# Bats-n-Gons2.net
KiCad netlist of a schematic drawn in EAGLE
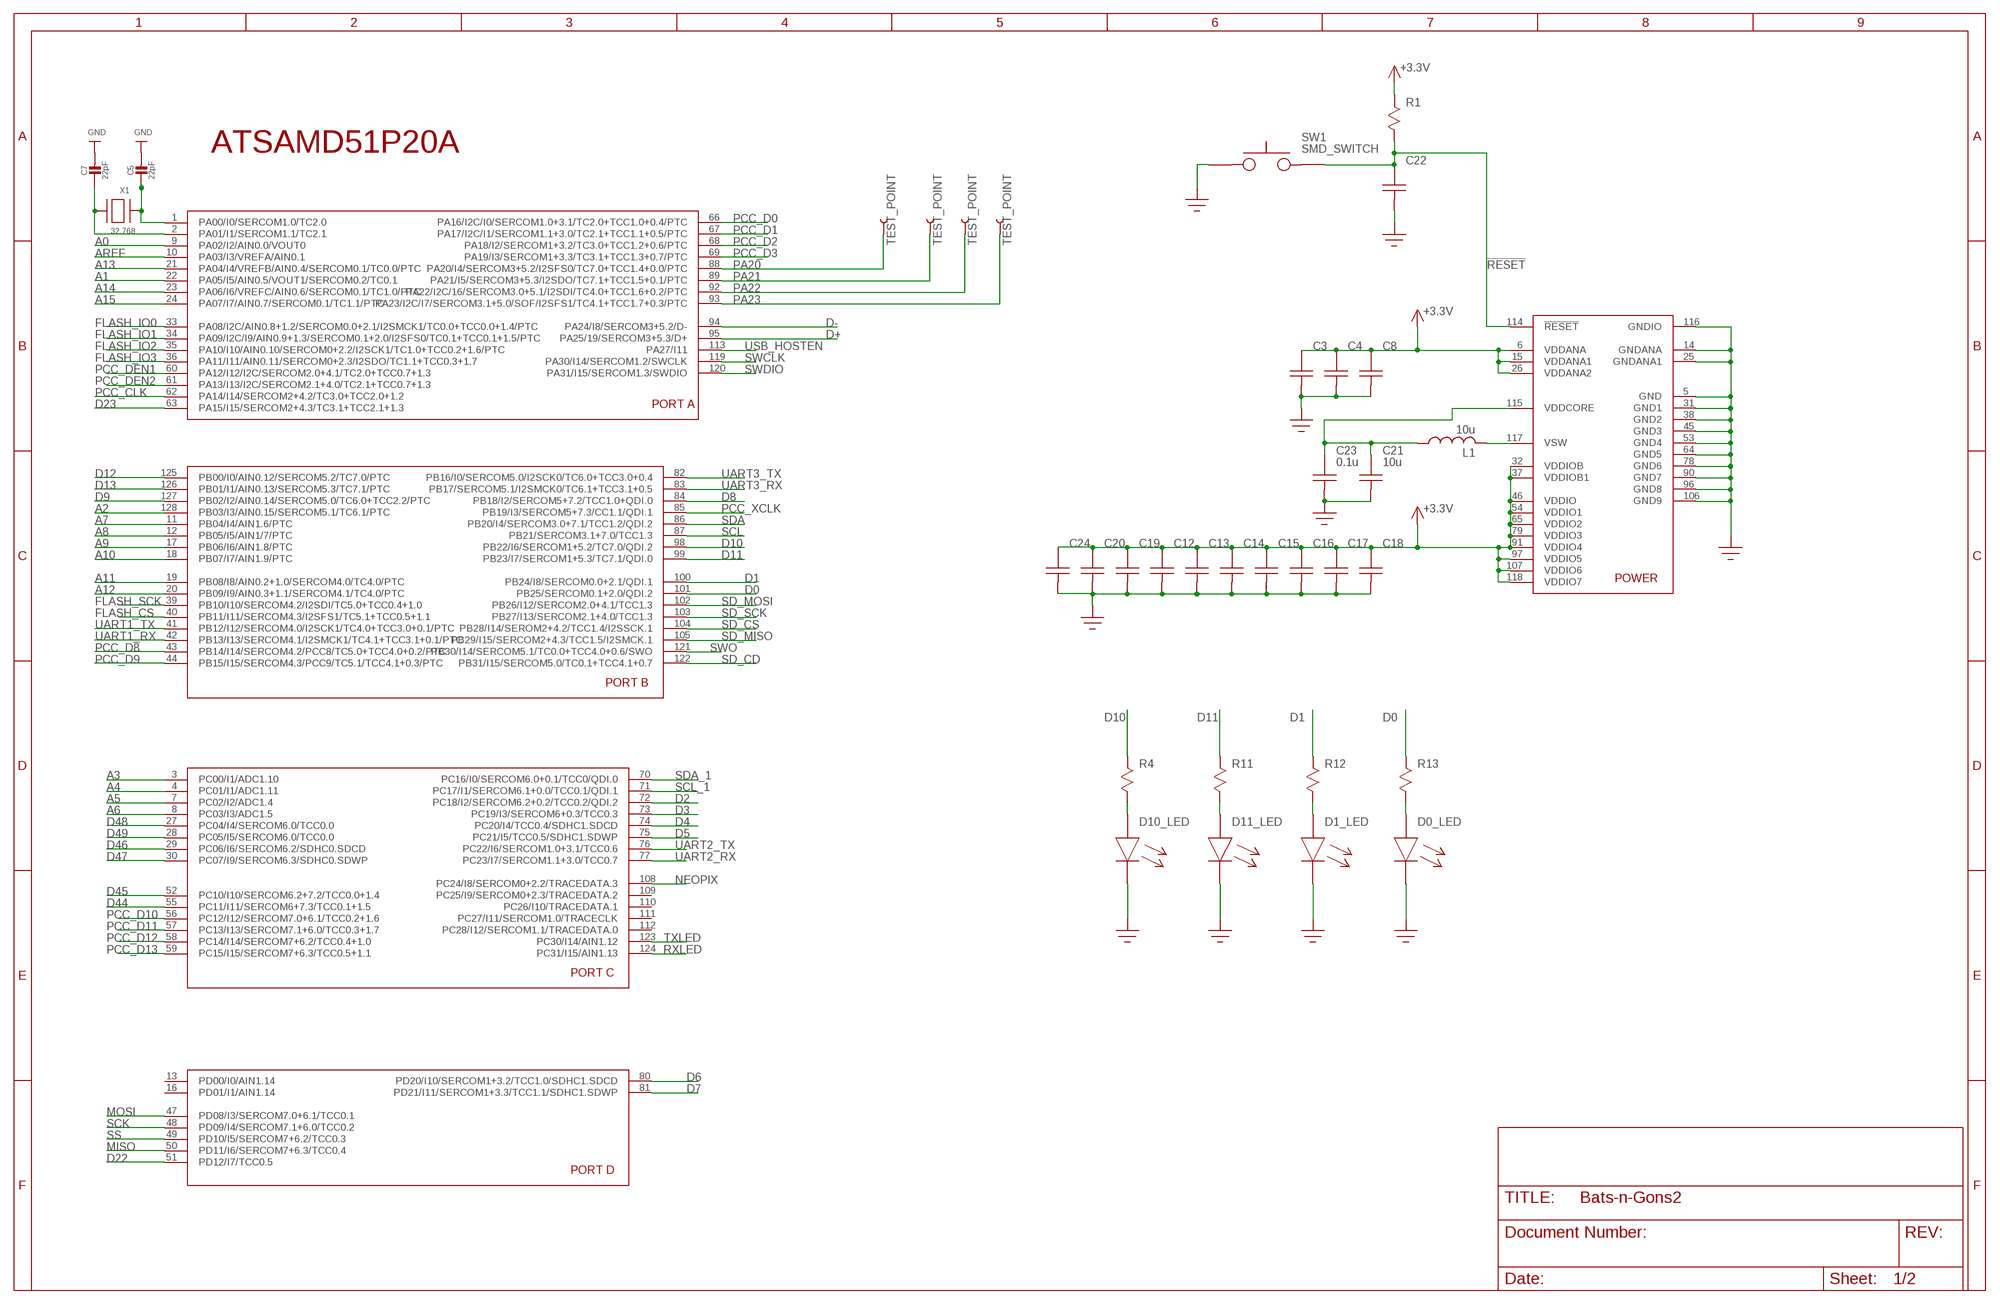
[diagram p0: schematic, sheet 1]
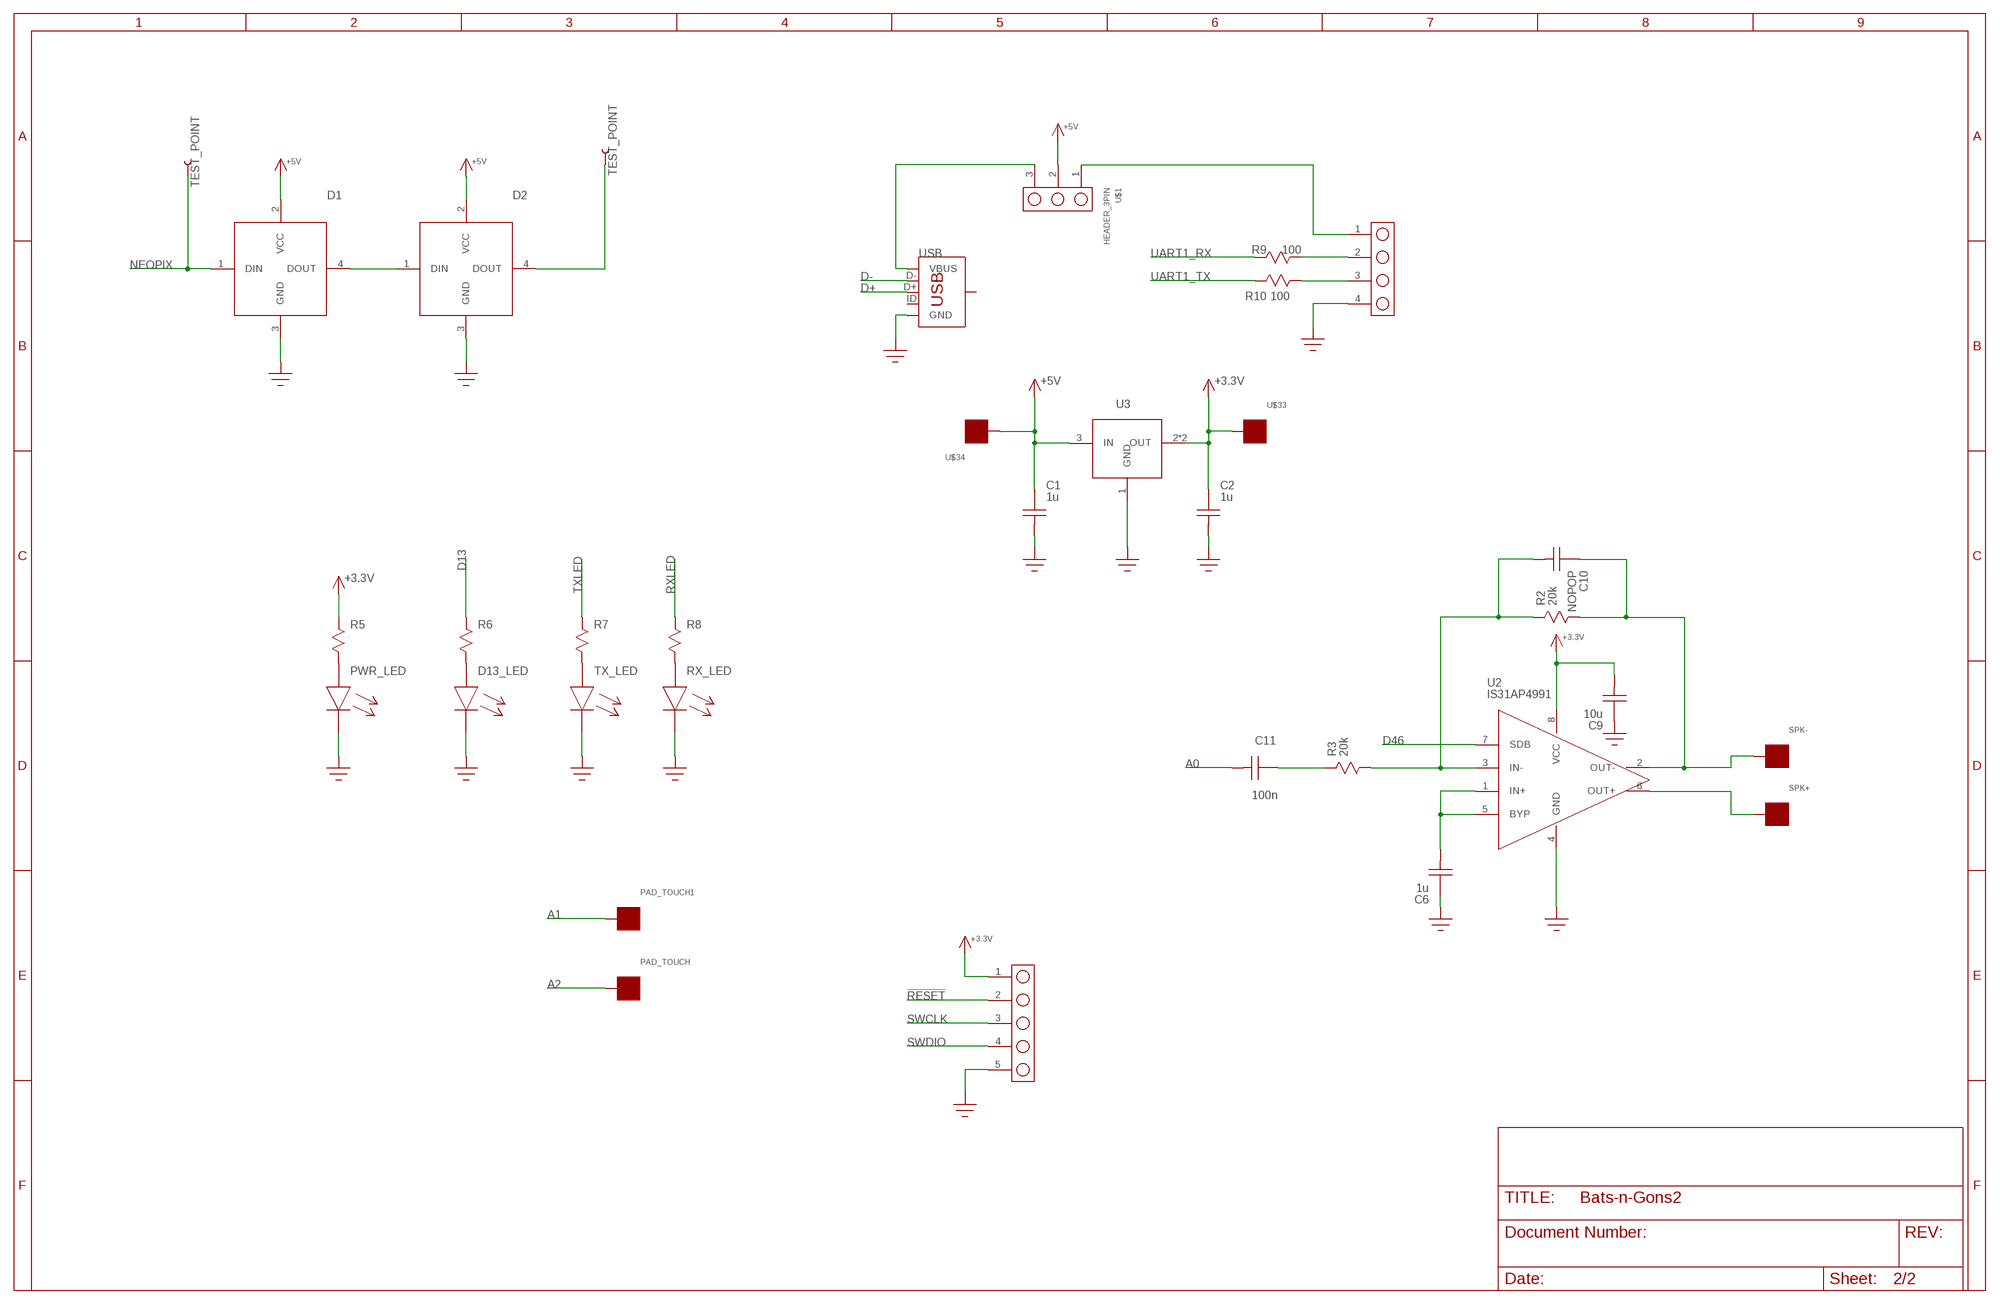
[diagram p1: schematic, sheet 2]

(export (version "E")
  (design (tool "Eeschema 10.0.6"))
  (components
    (comp (ref "C1")
      (value "1u")
      (footprint "eagle-import:C0603")
      (libsource (lib "eagle-import") (part "yapo_C0603"))
    )
    (comp (ref "C2")
      (value "1u")
      (footprint "eagle-import:C0603")
      (libsource (lib "eagle-import") (part "yapo_C0603"))
    )
    (comp (ref "C6")
      (value "1u")
      (footprint "eagle-import:C0603")
      (libsource (lib "eagle-import") (part "C0603"))
    )
    (comp (ref "C9")
      (value "10u")
      (footprint "eagle-import:1206")
      (libsource (lib "eagle-import") (part "C1206"))
    )
    (comp (ref "C10")
      (value "NOPOP")
      (footprint "eagle-import:C0603")
      (libsource (lib "eagle-import") (part "C0603"))
    )
    (comp (ref "C11")
      (value "100n")
      (footprint "eagle-import:C0603")
      (libsource (lib "eagle-import") (part "C0603"))
    )
    (comp (ref "D1")
      (value "NEOPIXEL")
      (footprint "eagle-import:LED-RGB-THRU")
      (libsource (lib "eagle-import") (part "NEOPIXEL"))
    )
    (comp (ref "D2")
      (value "NEOPIXEL")
      (footprint "eagle-import:LED-RGB-THRU")
      (libsource (lib "eagle-import") (part "NEOPIXEL"))
    )
    (comp (ref "D13_LED")
      (value "LED_0603")
      (footprint "eagle-import:LED_0603")
      (libsource (lib "eagle-import") (part "LED_0603"))
    )
    (comp (ref "DIN")
      (value "TEST_POINT")
      (footprint "eagle-import:TEST_POINT_LARGE")
      (libsource (lib "eagle-import") (part "TEST_POINT"))
    )
    (comp (ref "DOUT")
      (value "TEST_POINT")
      (footprint "eagle-import:TEST_POINT_LARGE")
      (libsource (lib "eagle-import") (part "TEST_POINT"))
    )
    (comp (ref "J1")
      (value "HEADER_4PIN")
      (footprint "eagle-import:HEADER_4PIN")
      (libsource (lib "eagle-import") (part "HEADER_4PIN"))
    )
    (comp (ref "J2")
      (value "HEADER_5PIN")
      (footprint "eagle-import:HEADER_5PIN")
      (libsource (lib "eagle-import") (part "HEADER_5PIN"))
    )
    (comp (ref "PAD_TOUCH")
      (value "PAD")
      (footprint "eagle-import:PAD-ROUND-100MIL-MASK")
      (libsource (lib "eagle-import") (part "PAD"))
    )
    (comp (ref "PAD_TOUCH1")
      (value "PAD")
      (footprint "eagle-import:PAD-ROUND-100MIL-MASK")
      (libsource (lib "eagle-import") (part "PAD"))
    )
    (comp (ref "PWR_LED")
      (value "LED_0603")
      (footprint "eagle-import:LED_0603")
      (libsource (lib "eagle-import") (part "LED_0603"))
    )
    (comp (ref "R2")
      (value "20k")
      (footprint "eagle-import:R0603")
      (libsource (lib "eagle-import") (part "R0603"))
    )
    (comp (ref "R3")
      (value "20k")
      (footprint "eagle-import:R0603")
      (libsource (lib "eagle-import") (part "R0603"))
    )
    (comp (ref "R5")
      (value "R0603")
      (footprint "eagle-import:R0603")
      (libsource (lib "eagle-import") (part "R0603"))
    )
    (comp (ref "R6")
      (value "R0603")
      (footprint "eagle-import:R0603")
      (libsource (lib "eagle-import") (part "R0603"))
    )
    (comp (ref "R7")
      (value "R0603")
      (footprint "eagle-import:R0603")
      (libsource (lib "eagle-import") (part "R0603"))
    )
    (comp (ref "R8")
      (value "R0603")
      (footprint "eagle-import:R0603")
      (libsource (lib "eagle-import") (part "R0603"))
    )
    (comp (ref "R9")
      (value "100")
      (footprint "eagle-import:R0603")
      (libsource (lib "eagle-import") (part "R0603"))
    )
    (comp (ref "R10")
      (value "100")
      (footprint "eagle-import:R0603")
      (libsource (lib "eagle-import") (part "R0603"))
    )
    (comp (ref "RX_LED")
      (value "LED_0603")
      (footprint "eagle-import:LED_0603")
      (libsource (lib "eagle-import") (part "LED_0603"))
    )
    (comp (ref "SPK+")
      (value "PAD100MIL")
      (footprint "eagle-import:PAD_100MIL")
      (libsource (lib "eagle-import") (part "PAD100MIL"))
    )
    (comp (ref "SPK-")
      (value "PAD100MIL")
      (footprint "eagle-import:PAD_100MIL")
      (libsource (lib "eagle-import") (part "PAD100MIL"))
    )
    (comp (ref "TX_LED")
      (value "LED_0603")
      (footprint "eagle-import:LED_0603")
      (libsource (lib "eagle-import") (part "LED_0603"))
    )
    (comp (ref "U$1")
      (value "HEADER_3PIN")
      (footprint "eagle-import:HEADER_3PIN")
      (libsource (lib "eagle-import") (part "HEADER_3PIN"))
    )
    (comp (ref "U$33")
      (value "PADROUND-50MIL")
      (footprint "eagle-import:PAD-ROUND-50MIL")
      (libsource (lib "eagle-import") (part "PADROUND-50MIL"))
    )
    (comp (ref "U$34")
      (value "PADROUND-50MIL")
      (footprint "eagle-import:PAD-ROUND-50MIL")
      (libsource (lib "eagle-import") (part "PADROUND-50MIL"))
    )
    (comp (ref "U2")
      (value "IS31AP4991")
      (footprint "eagle-import:SOIC8")
      (libsource (lib "eagle-import") (part "IS31AP4991SOIC"))
    )
    (comp (ref "U3")
      (value "AZ1117E")
      (footprint "eagle-import:SOT-223")
      (libsource (lib "eagle-import") (part "AZ1117E"))
    )
    (comp (ref "USB")
      (value "USB_MICRO_LEGS")
      (footprint "eagle-import:USB_MICRO_LEGS_2")
      (libsource (lib "eagle-import") (part "USB_MICRO_LEGS"))
    )
    (comp (ref "C3")
      (value "C0603")
      (footprint "eagle-import:C0603")
      (libsource (lib "eagle-import") (part "C0603"))
    )
    (comp (ref "C4")
      (value "C0603")
      (footprint "eagle-import:C0603")
      (libsource (lib "eagle-import") (part "C0603"))
    )
    (comp (ref "C5")
      (value "22pF")
      (footprint "eagle-import:0603-NO")
      (libsource (lib "eagle-import") (part "CAP_CERAMIC0603_NO"))
    )
    (comp (ref "C7")
      (value "22pF")
      (footprint "eagle-import:0603-NO")
      (libsource (lib "eagle-import") (part "CAP_CERAMIC0603_NO"))
    )
    (comp (ref "C8")
      (value "C0603")
      (footprint "eagle-import:C0603")
      (libsource (lib "eagle-import") (part "C0603"))
    )
    (comp (ref "C12")
      (value "C0603")
      (footprint "eagle-import:C0603")
      (libsource (lib "eagle-import") (part "C0603"))
    )
    (comp (ref "C13")
      (value "C0603")
      (footprint "eagle-import:C0603")
      (libsource (lib "eagle-import") (part "C0603"))
    )
    (comp (ref "C14")
      (value "C0603")
      (footprint "eagle-import:C0603")
      (libsource (lib "eagle-import") (part "C0603"))
    )
    (comp (ref "C15")
      (value "C0603")
      (footprint "eagle-import:C0603")
      (libsource (lib "eagle-import") (part "C0603"))
    )
    (comp (ref "C16")
      (value "C0603")
      (footprint "eagle-import:C0603")
      (libsource (lib "eagle-import") (part "C0603"))
    )
    (comp (ref "C17")
      (value "C0603")
      (footprint "eagle-import:C0603")
      (libsource (lib "eagle-import") (part "C0603"))
    )
    (comp (ref "C18")
      (value "C0603")
      (footprint "eagle-import:C0603")
      (libsource (lib "eagle-import") (part "C0603"))
    )
    (comp (ref "C19")
      (value "C0603")
      (footprint "eagle-import:C0603")
      (libsource (lib "eagle-import") (part "C0603"))
    )
    (comp (ref "C20")
      (value "C0603")
      (footprint "eagle-import:C0603")
      (libsource (lib "eagle-import") (part "C0603"))
    )
    (comp (ref "C21")
      (value "10u")
      (footprint "eagle-import:C0603")
      (libsource (lib "eagle-import") (part "C0603"))
    )
    (comp (ref "C22")
      (value "C0603")
      (footprint "eagle-import:C0603")
      (libsource (lib "eagle-import") (part "C0603"))
    )
    (comp (ref "C23")
      (value "0.1u")
      (footprint "eagle-import:C0603")
      (libsource (lib "eagle-import") (part "C0603"))
    )
    (comp (ref "C24")
      (value "C0603")
      (footprint "eagle-import:C0603")
      (libsource (lib "eagle-import") (part "C0603"))
    )
    (comp (ref "D0_LED")
      (value "LED_0603")
      (footprint "eagle-import:LED_0603")
      (libsource (lib "eagle-import") (part "LED_0603"))
    )
    (comp (ref "D1_LED")
      (value "LED_0603")
      (footprint "eagle-import:LED_0603")
      (libsource (lib "eagle-import") (part "LED_0603"))
    )
    (comp (ref "D10_LED")
      (value "LED_0603")
      (footprint "eagle-import:LED_0603")
      (libsource (lib "eagle-import") (part "LED_0603"))
    )
    (comp (ref "D11_LED")
      (value "LED_0603")
      (footprint "eagle-import:LED_0603")
      (libsource (lib "eagle-import") (part "LED_0603"))
    )
    (comp (ref "L1")
      (value "10u")
      (footprint "eagle-import:L24X24")
      (libsource (lib "eagle-import") (part "INDUCTOR2424"))
    )
    (comp (ref "R1")
      (value "R0603")
      (footprint "eagle-import:R0603")
      (libsource (lib "eagle-import") (part "R0603"))
    )
    (comp (ref "R4")
      (value "R0603")
      (footprint "eagle-import:R0603")
      (libsource (lib "eagle-import") (part "R0603"))
    )
    (comp (ref "R11")
      (value "R0603")
      (footprint "eagle-import:R0603")
      (libsource (lib "eagle-import") (part "R0603"))
    )
    (comp (ref "R12")
      (value "R0603")
      (footprint "eagle-import:R0603")
      (libsource (lib "eagle-import") (part "R0603"))
    )
    (comp (ref "R13")
      (value "R0603")
      (footprint "eagle-import:R0603")
      (libsource (lib "eagle-import") (part "R0603"))
    )
    (comp (ref "SW1")
      (value "SMD_SWITCH")
      (footprint "eagle-import:SMD_SWITCH")
      (libsource (lib "eagle-import") (part "SMD_SWITCH"))
    )
    (comp (ref "U$38")
      (value "TEST_POINT")
      (footprint "eagle-import:TEST_POINT_LARGE")
      (libsource (lib "eagle-import") (part "TEST_POINT"))
    )
    (comp (ref "U$39")
      (value "TEST_POINT")
      (footprint "eagle-import:TEST_POINT_LARGE")
      (libsource (lib "eagle-import") (part "TEST_POINT"))
    )
    (comp (ref "U$40")
      (value "TEST_POINT")
      (footprint "eagle-import:TEST_POINT_LARGE")
      (libsource (lib "eagle-import") (part "TEST_POINT"))
    )
    (comp (ref "U$41")
      (value "TEST_POINT")
      (footprint "eagle-import:TEST_POINT_LARGE")
      (libsource (lib "eagle-import") (part "TEST_POINT"))
    )
    (comp (ref "U1")
      (value "SAMD51PXXA")
      (footprint "eagle-import:SQFP-S-14X14-128")
      (libsource (lib "eagle-import") (part "SAMD51PXXA"))
    )
    (comp (ref "X1")
      (value "32.768")
      (footprint "eagle-import:XTAL3215")
      (libsource (lib "eagle-import") (part "XTAL-3.2X1.5"))
    )
  )
  (nets
    (net (code "1") (name "+3.3V") (class "Default")
      (node (ref "C12") (pin "P$2") (pinfunction "P$2_P$2") (pintype "bidirectional"))
      (node (ref "C13") (pin "P$2") (pinfunction "P$2_P$2") (pintype "bidirectional"))
      (node (ref "C14") (pin "P$2") (pinfunction "P$2_P$2") (pintype "bidirectional"))
      (node (ref "C15") (pin "P$2") (pinfunction "P$2_P$2") (pintype "bidirectional"))
      (node (ref "C16") (pin "P$2") (pinfunction "P$2_P$2") (pintype "bidirectional"))
      (node (ref "C17") (pin "P$2") (pinfunction "P$2_P$2") (pintype "bidirectional"))
      (node (ref "C18") (pin "P$2") (pinfunction "P$2_P$2") (pintype "bidirectional"))
      (node (ref "C19") (pin "P$2") (pinfunction "P$2_P$2") (pintype "bidirectional"))
      (node (ref "C2") (pin "P$2") (pinfunction "P$2_P$2") (pintype "bidirectional"))
      (node (ref "C20") (pin "P$2") (pinfunction "P$2_P$2") (pintype "bidirectional"))
      (node (ref "C24") (pin "P$2") (pinfunction "P$2_P$2") (pintype "bidirectional"))
      (node (ref "C3") (pin "P$2") (pinfunction "P$2_P$2") (pintype "bidirectional"))
      (node (ref "C4") (pin "P$2") (pinfunction "P$2_P$2") (pintype "bidirectional"))
      (node (ref "C8") (pin "P$2") (pinfunction "P$2_P$2") (pintype "bidirectional"))
      (node (ref "C9") (pin "P$1") (pinfunction "P$1_P$1") (pintype "bidirectional"))
      (node (ref "J2") (pin "1") (pinfunction "1_1") (pintype "bidirectional"))
      (node (ref "R1") (pin "P$1") (pinfunction "P$3_P$1") (pintype "bidirectional"))
      (node (ref "R5") (pin "P$1") (pinfunction "P$3_P$1") (pintype "bidirectional"))
      (node (ref "U$33") (pin "P$1") (pinfunction "P$1_P$1") (pintype "bidirectional"))
      (node (ref "U1") (pin "107") (pinfunction "VDDIO6_107") (pintype "bidirectional"))
      (node (ref "U1") (pin "118") (pinfunction "VDDIO7_118") (pintype "bidirectional"))
      (node (ref "U1") (pin "15") (pinfunction "VDDANA1_15") (pintype "bidirectional"))
      (node (ref "U1") (pin "26") (pinfunction "VDDANA2_26") (pintype "bidirectional"))
      (node (ref "U1") (pin "32") (pinfunction "VDDIOB_32") (pintype "bidirectional"))
      (node (ref "U1") (pin "37") (pinfunction "VDDIOB1_37") (pintype "bidirectional"))
      (node (ref "U1") (pin "46") (pinfunction "VDDIO_46") (pintype "bidirectional"))
      (node (ref "U1") (pin "54") (pinfunction "VDDIO1_54") (pintype "bidirectional"))
      (node (ref "U1") (pin "6") (pinfunction "VDDANA_6") (pintype "bidirectional"))
      (node (ref "U1") (pin "65") (pinfunction "VDDIO2_65") (pintype "bidirectional"))
      (node (ref "U1") (pin "79") (pinfunction "VDDIO3_79") (pintype "bidirectional"))
      (node (ref "U1") (pin "91") (pinfunction "VDDIO4_91") (pintype "bidirectional"))
      (node (ref "U1") (pin "97") (pinfunction "VDDIO5_97") (pintype "bidirectional"))
      (node (ref "U2") (pin "8") (pinfunction "VCC_8") (pintype "bidirectional"))
      (node (ref "U3") (pin "2") (pinfunction "OUT_2") (pintype "bidirectional"))
      (node (ref "U3") (pin "4") (pinfunction "OUT_4") (pintype "bidirectional"))
    )
    (net (code "2") (name "+5V") (class "Default")
      (node (ref "C1") (pin "P$2") (pinfunction "P$2_P$2") (pintype "bidirectional"))
      (node (ref "D1") (pin "2") (pinfunction "VCC_2") (pintype "bidirectional"))
      (node (ref "D2") (pin "2") (pinfunction "VCC_2") (pintype "bidirectional"))
      (node (ref "U$1") (pin "2") (pinfunction "2_2") (pintype "bidirectional"))
      (node (ref "U$34") (pin "P$1") (pinfunction "P$1_P$1") (pintype "bidirectional"))
      (node (ref "U3") (pin "3") (pinfunction "IN_3") (pintype "bidirectional"))
    )
    (net (code "3") (name "A0") (class "Default")
      (node (ref "C11") (pin "P$1") (pinfunction "P$1_P$1") (pintype "bidirectional"))
      (node (ref "U1") (pin "9") (pinfunction "PA02/I2/AIN0.0/VOUT0_9") (pintype "bidirectional"))
    )
    (net (code "4") (name "A1") (class "Default")
      (node (ref "PAD_TOUCH1") (pin "P$1") (pinfunction "P$1_P$1") (pintype "bidirectional"))
      (node (ref "U1") (pin "22") (pinfunction "PA05/I5/AIN0.5/VOUT1/SERCOM0.2/TC0.1_22") (pintype "bidirectional"))
    )
    (net (code "5") (name "A2") (class "Default")
      (node (ref "PAD_TOUCH") (pin "P$1") (pinfunction "P$1_P$1") (pintype "bidirectional"))
      (node (ref "U1") (pin "128") (pinfunction "PB03/I3/AIN0.15/SERCOM5.1/TC6.1/PTC_128") (pintype "bidirectional"))
    )
    (net (code "6") (name "A3") (class "Default")
      (node (ref "U1") (pin "3") (pinfunction "PC00/I1/ADC1.10_3") (pintype "bidirectional"))
    )
    (net (code "7") (name "A4") (class "Default")
      (node (ref "U1") (pin "4") (pinfunction "PC01/I1/ADC1.11_4") (pintype "bidirectional"))
    )
    (net (code "8") (name "A5") (class "Default")
      (node (ref "U1") (pin "7") (pinfunction "PC02/I2/ADC1.4_7") (pintype "bidirectional"))
    )
    (net (code "9") (name "A6") (class "Default")
      (node (ref "U1") (pin "8") (pinfunction "PC03/I3/ADC1.5_8") (pintype "bidirectional"))
    )
    (net (code "10") (name "A7") (class "Default")
      (node (ref "U1") (pin "11") (pinfunction "PB04/I4/AIN1.6/PTC_11") (pintype "bidirectional"))
    )
    (net (code "11") (name "A8") (class "Default")
      (node (ref "U1") (pin "12") (pinfunction "PB05/I5/AIN1/7/PTC_12") (pintype "bidirectional"))
    )
    (net (code "12") (name "A9") (class "Default")
      (node (ref "U1") (pin "17") (pinfunction "PB06/I6/AIN1.8/PTC_17") (pintype "bidirectional"))
    )
    (net (code "13") (name "A10") (class "Default")
      (node (ref "U1") (pin "18") (pinfunction "PB07/I7/AIN1.9/PTC_18") (pintype "bidirectional"))
    )
    (net (code "14") (name "A11") (class "Default")
      (node (ref "U1") (pin "19") (pinfunction "PB08/I8/AIN0.2+1.0/SERCOM4.0/TC4.0/PTC_19") (pintype "bidirectional"))
    )
    (net (code "15") (name "A12") (class "Default")
      (node (ref "U1") (pin "20") (pinfunction "PB09/I9/AIN0.3+1.1/SERCOM4.1/TC4.0/PTC_20") (pintype "bidirectional"))
    )
    (net (code "16") (name "A13") (class "Default")
      (node (ref "U1") (pin "21") (pinfunction "PA04/I4/VREFB/AIN0.4/SERCOM0.1/TC0.0/PTC_21") (pintype "bidirectional"))
    )
    (net (code "17") (name "A14") (class "Default")
      (node (ref "U1") (pin "23") (pinfunction "PA06/I6/VREFC/AIN0.6/SERCOM0.1/TC1.0/PTC_23") (pintype "bidirectional"))
    )
    (net (code "18") (name "A15") (class "Default")
      (node (ref "U1") (pin "24") (pinfunction "PA07/I7/AIN0.7/SERCOM0.1/TC1.1/PTC_24") (pintype "bidirectional"))
    )
    (net (code "19") (name "AREF") (class "Default")
      (node (ref "U1") (pin "10") (pinfunction "PA03/I3/VREFA/AIN0.1_10") (pintype "bidirectional"))
    )
    (net (code "20") (name "D+") (class "Default")
      (node (ref "U1") (pin "95") (pinfunction "PA25/19/SERCOM3+5.3/D+_95") (pintype "bidirectional"))
      (node (ref "USB") (pin "D+") (pinfunction "D+_D+") (pintype "bidirectional"))
    )
    (net (code "21") (name "D-") (class "Default")
      (node (ref "U1") (pin "94") (pinfunction "PA24/I8/SERCOM3+5.2/D-_94") (pintype "bidirectional"))
      (node (ref "USB") (pin "D-") (pinfunction "D-_D-") (pintype "bidirectional"))
    )
    (net (code "22") (name "D0") (class "Default")
      (node (ref "R13") (pin "P$1") (pinfunction "P$3_P$1") (pintype "bidirectional"))
      (node (ref "U1") (pin "101") (pinfunction "PB25/SERCOM0.1+2.0/QDI.2_101") (pintype "bidirectional"))
    )
    (net (code "23") (name "D1") (class "Default")
      (node (ref "R12") (pin "P$1") (pinfunction "P$3_P$1") (pintype "bidirectional"))
      (node (ref "U1") (pin "100") (pinfunction "PB24/I8/SERCOM0.0+2.1/QDI.1_100") (pintype "bidirectional"))
    )
    (net (code "24") (name "D2") (class "Default")
      (node (ref "U1") (pin "72") (pinfunction "PC18/I2/SERCOM6.2+0.2/TCC0.2/QDI.2_72") (pintype "bidirectional"))
    )
    (net (code "25") (name "D3") (class "Default")
      (node (ref "U1") (pin "73") (pinfunction "PC19/I3/SERCOM6+0.3/TCC0.3_73") (pintype "bidirectional"))
    )
    (net (code "26") (name "D4") (class "Default")
      (node (ref "U1") (pin "74") (pinfunction "PC20/I4/TCC0.4/SDHC1.SDCD_74") (pintype "bidirectional"))
    )
    (net (code "27") (name "D5") (class "Default")
      (node (ref "U1") (pin "75") (pinfunction "PC21/I5/TCC0.5/SDHC1.SDWP_75") (pintype "bidirectional"))
    )
    (net (code "28") (name "D6") (class "Default")
      (node (ref "U1") (pin "80") (pinfunction "PD20/I10/SERCOM1+3.2/TCC1.0/SDHC1.SDCD_80") (pintype "bidirectional"))
    )
    (net (code "29") (name "D7") (class "Default")
      (node (ref "U1") (pin "81") (pinfunction "PD21/I11/SERCOM1+3.3/TCC1.1/SDHC1.SDWP_81") (pintype "bidirectional"))
    )
    (net (code "30") (name "D8") (class "Default")
      (node (ref "U1") (pin "84") (pinfunction "PB18/I2/SERCOM5+7.2/TCC1.0+QDI.0_84") (pintype "bidirectional"))
    )
    (net (code "31") (name "D9") (class "Default")
      (node (ref "U1") (pin "127") (pinfunction "PB02/I2/AIN0.14/SERCOM5.0/TC6.0+TCC2.2/PTC_127") (pintype "bidirectional"))
    )
    (net (code "32") (name "D10") (class "Default")
      (node (ref "R4") (pin "P$1") (pinfunction "P$3_P$1") (pintype "bidirectional"))
      (node (ref "U1") (pin "98") (pinfunction "PB22/I6/SERCOM1+5.2/TC7.0/QDI.2_98") (pintype "bidirectional"))
    )
    (net (code "33") (name "D11") (class "Default")
      (node (ref "R11") (pin "P$1") (pinfunction "P$3_P$1") (pintype "bidirectional"))
      (node (ref "U1") (pin "99") (pinfunction "PB23/I7/SERCOM1+5.3/TC7.1/QDI.0_99") (pintype "bidirectional"))
    )
    (net (code "34") (name "D12") (class "Default")
      (node (ref "U1") (pin "125") (pinfunction "PB00/I0/AIN0.12/SERCOM5.2/TC7.0/PTC_125") (pintype "bidirectional"))
    )
    (net (code "35") (name "D13") (class "Default")
      (node (ref "R6") (pin "P$1") (pinfunction "P$3_P$1") (pintype "bidirectional"))
      (node (ref "U1") (pin "126") (pinfunction "PB01/I1/AIN0.13/SERCOM5.3/TC7.1/PTC_126") (pintype "bidirectional"))
    )
    (net (code "36") (name "D22") (class "Default")
      (node (ref "U1") (pin "51") (pinfunction "PD12/I7/TCC0.5_51") (pintype "bidirectional"))
    )
    (net (code "37") (name "D23") (class "Default")
      (node (ref "U1") (pin "63") (pinfunction "PA15/I15/SERCOM2+4.3/TC3.1+TCC2.1+1.3_63") (pintype "bidirectional"))
    )
    (net (code "38") (name "D44") (class "Default")
      (node (ref "U1") (pin "55") (pinfunction "PC11/I11/SERCOM6+7.3/TCC0.1+1.5_55") (pintype "bidirectional"))
    )
    (net (code "39") (name "D45") (class "Default")
      (node (ref "U1") (pin "52") (pinfunction "PC10/I10/SERCOM6.2+7.2/TCC0.0+1.4_52") (pintype "bidirectional"))
    )
    (net (code "40") (name "D46") (class "Default")
      (node (ref "U1") (pin "29") (pinfunction "PC06/I6/SERCOM6.2/SDHC0.SDCD_29") (pintype "bidirectional"))
      (node (ref "U2") (pin "7") (pinfunction "SDB_7") (pintype "bidirectional"))
    )
    (net (code "41") (name "D47") (class "Default")
      (node (ref "U1") (pin "30") (pinfunction "PC07/I9/SERCOM6.3/SDHC0.SDWP_30") (pintype "bidirectional"))
    )
    (net (code "42") (name "D48") (class "Default")
      (node (ref "U1") (pin "27") (pinfunction "PC04/I4/SERCOM6.0/TCC0.0_27") (pintype "bidirectional"))
    )
    (net (code "43") (name "D49") (class "Default")
      (node (ref "U1") (pin "28") (pinfunction "PC05/I5/SERCOM6.0/TCC0.0_28") (pintype "bidirectional"))
    )
    (net (code "44") (name "FLASH_CS") (class "Default")
      (node (ref "U1") (pin "40") (pinfunction "PB11/I11/SERCOM4.3/I2SFS1/TC5.1+TCC0.5+1.1_40") (pintype "bidirectional"))
    )
    (net (code "45") (name "FLASH_IO0") (class "Default")
      (node (ref "U1") (pin "33") (pinfunction "PA08/I2C/AIN0.8+1.2/SERCOM0.0+2.1/I2SMCK1/TC0.0+TCC0.0+1.4/PTC_33") (pintype "bidirectional"))
    )
    (net (code "46") (name "FLASH_IO1") (class "Default")
      (node (ref "U1") (pin "34") (pinfunction "PA09/I2C/I9/AIN0.9+1.3/SERCOM0.1+2.0/I2SFS0/TC0.1+TCC0.1+1.5/PTC_34") (pintype "bidirectional"))
    )
    (net (code "47") (name "FLASH_IO2") (class "Default")
      (node (ref "U1") (pin "35") (pinfunction "PA10/I10/AIN0.10/SERCOM0+2.2/I2SCK1/TC1.0+TCC0.2+1.6/PTC_35") (pintype "bidirectional"))
    )
    (net (code "48") (name "FLASH_IO3") (class "Default")
      (node (ref "U1") (pin "36") (pinfunction "PA11/I11/AIN0.11/SERCOM0+2.3/I2SDO/TC1.1+TCC0.3+1.7_36") (pintype "bidirectional"))
    )
    (net (code "49") (name "FLASH_SCK") (class "Default")
      (node (ref "U1") (pin "39") (pinfunction "PB10/I10/SERCOM4.2/I2SDI/TC5.0+TCC0.4+1.0_39") (pintype "bidirectional"))
    )
    (net (code "50") (name "GND") (class "Default")
      (node (ref "C1") (pin "P$1") (pinfunction "P$1_P$1") (pintype "bidirectional"))
      (node (ref "C12") (pin "P$1") (pinfunction "P$1_P$1") (pintype "bidirectional"))
      (node (ref "C13") (pin "P$1") (pinfunction "P$1_P$1") (pintype "bidirectional"))
      (node (ref "C14") (pin "P$1") (pinfunction "P$1_P$1") (pintype "bidirectional"))
      (node (ref "C15") (pin "P$1") (pinfunction "P$1_P$1") (pintype "bidirectional"))
      (node (ref "C16") (pin "P$1") (pinfunction "P$1_P$1") (pintype "bidirectional"))
      (node (ref "C17") (pin "P$1") (pinfunction "P$1_P$1") (pintype "bidirectional"))
      (node (ref "C18") (pin "P$1") (pinfunction "P$1_P$1") (pintype "bidirectional"))
      (node (ref "C19") (pin "P$1") (pinfunction "P$1_P$1") (pintype "bidirectional"))
      (node (ref "C2") (pin "P$1") (pinfunction "P$1_P$1") (pintype "bidirectional"))
      (node (ref "C20") (pin "P$1") (pinfunction "P$1_P$1") (pintype "bidirectional"))
      (node (ref "C21") (pin "P$1") (pinfunction "P$1_P$1") (pintype "bidirectional"))
      (node (ref "C22") (pin "P$1") (pinfunction "P$1_P$1") (pintype "bidirectional"))
      (node (ref "C23") (pin "P$1") (pinfunction "P$1_P$1") (pintype "bidirectional"))
      (node (ref "C24") (pin "P$1") (pinfunction "P$1_P$1") (pintype "bidirectional"))
      (node (ref "C3") (pin "P$1") (pinfunction "P$1_P$1") (pintype "bidirectional"))
      (node (ref "C4") (pin "P$1") (pinfunction "P$1_P$1") (pintype "bidirectional"))
      (node (ref "C5") (pin "2") (pinfunction "2_2") (pintype "passive"))
      (node (ref "C6") (pin "P$2") (pinfunction "P$2_P$2") (pintype "bidirectional"))
      (node (ref "C7") (pin "2") (pinfunction "2_2") (pintype "passive"))
      (node (ref "C8") (pin "P$1") (pinfunction "P$1_P$1") (pintype "bidirectional"))
      (node (ref "C9") (pin "P$2") (pinfunction "P$2_P$2") (pintype "bidirectional"))
      (node (ref "D0_LED") (pin "C") (pinfunction "C_C") (pintype "bidirectional"))
      (node (ref "D1") (pin "3") (pinfunction "GND_3") (pintype "bidirectional"))
      (node (ref "D10_LED") (pin "C") (pinfunction "C_C") (pintype "bidirectional"))
      (node (ref "D11_LED") (pin "C") (pinfunction "C_C") (pintype "bidirectional"))
      (node (ref "D13_LED") (pin "C") (pinfunction "C_C") (pintype "bidirectional"))
      (node (ref "D1_LED") (pin "C") (pinfunction "C_C") (pintype "bidirectional"))
      (node (ref "D2") (pin "3") (pinfunction "GND_3") (pintype "bidirectional"))
      (node (ref "J1") (pin "4") (pinfunction "4_4") (pintype "bidirectional"))
      (node (ref "J2") (pin "5") (pinfunction "5_5") (pintype "bidirectional"))
      (node (ref "PWR_LED") (pin "C") (pinfunction "C_C") (pintype "bidirectional"))
      (node (ref "RX_LED") (pin "C") (pinfunction "C_C") (pintype "bidirectional"))
      (node (ref "SW1") (pin "P$1") (pinfunction "P$1_P$1") (pintype "bidirectional"))
      (node (ref "SW1") (pin "P$2") (pinfunction "P$1_P$2") (pintype "bidirectional"))
      (node (ref "TX_LED") (pin "C") (pinfunction "C_C") (pintype "bidirectional"))
      (node (ref "U1") (pin "106") (pinfunction "GND9_106") (pintype "bidirectional"))
      (node (ref "U1") (pin "116") (pinfunction "GNDIO_116") (pintype "bidirectional"))
      (node (ref "U1") (pin "14") (pinfunction "GNDANA_14") (pintype "bidirectional"))
      (node (ref "U1") (pin "25") (pinfunction "GNDANA1_25") (pintype "bidirectional"))
      (node (ref "U1") (pin "31") (pinfunction "GND1_31") (pintype "bidirectional"))
      (node (ref "U1") (pin "38") (pinfunction "GND2_38") (pintype "bidirectional"))
      (node (ref "U1") (pin "45") (pinfunction "GND3_45") (pintype "bidirectional"))
      (node (ref "U1") (pin "5") (pinfunction "GND_5") (pintype "bidirectional"))
      (node (ref "U1") (pin "53") (pinfunction "GND4_53") (pintype "bidirectional"))
      (node (ref "U1") (pin "64") (pinfunction "GND5_64") (pintype "bidirectional"))
      (node (ref "U1") (pin "78") (pinfunction "GND6_78") (pintype "bidirectional"))
      (node (ref "U1") (pin "90") (pinfunction "GND7_90") (pintype "bidirectional"))
      (node (ref "U1") (pin "96") (pinfunction "GND8_96") (pintype "bidirectional"))
      (node (ref "U2") (pin "4") (pinfunction "GND_4") (pintype "bidirectional"))
      (node (ref "U3") (pin "1") (pinfunction "GND_1") (pintype "bidirectional"))
      (node (ref "USB") (pin "GND") (pinfunction "GND_GND") (pintype "power_in"))
    )
    (net (code "51") (name "MISO") (class "Default")
      (node (ref "U1") (pin "50") (pinfunction "PD11/I6/SERCOM7+6.3/TCC0.4_50") (pintype "bidirectional"))
    )
    (net (code "52") (name "MOSI") (class "Default")
      (node (ref "U1") (pin "47") (pinfunction "PD08/I3/SERCOM7.0+6.1/TCC0.1_47") (pintype "bidirectional"))
    )
    (net (code "53") (name "NEOPIX") (class "Default")
      (node (ref "D1") (pin "1") (pinfunction "DIN_1") (pintype "bidirectional"))
      (node (ref "DIN") (pin "P$1") (pinfunction "1_P$1") (pintype "bidirectional"))
      (node (ref "U1") (pin "108") (pinfunction "PC24/I8/SERCOM0+2.2/TRACEDATA.3_108") (pintype "bidirectional"))
    )
    (net (code "54") (name "Net-(D1-DOUT)") (class "Default")
      (node (ref "D1") (pin "4") (pinfunction "DOUT_4") (pintype "bidirectional"))
      (node (ref "D2") (pin "1") (pinfunction "DIN_1") (pintype "bidirectional"))
    )
    (net (code "55") (name "Net-(D2-DOUT)") (class "Default")
      (node (ref "D2") (pin "4") (pinfunction "DOUT_4") (pintype "bidirectional"))
      (node (ref "DOUT") (pin "P$1") (pinfunction "1_P$1") (pintype "bidirectional"))
    )
    (net (code "56") (name "Net-(J1-Pad1)") (class "Default")
      (node (ref "J1") (pin "1") (pinfunction "1_1") (pintype "bidirectional"))
      (node (ref "U$1") (pin "1") (pinfunction "1_1") (pintype "bidirectional"))
    )
    (net (code "57") (name "Net-(R2-P$3)") (class "Default")
      (node (ref "C10") (pin "P$1") (pinfunction "P$1_P$1") (pintype "bidirectional"))
      (node (ref "R2") (pin "P$1") (pinfunction "P$3_P$1") (pintype "bidirectional"))
      (node (ref "R3") (pin "P$2") (pinfunction "P$4_P$2") (pintype "bidirectional"))
      (node (ref "U2") (pin "3") (pinfunction "IN-_3") (pintype "bidirectional"))
    )
    (net (code "58") (name "Net-(R2-P$4)") (class "Default")
      (node (ref "C10") (pin "P$2") (pinfunction "P$2_P$2") (pintype "bidirectional"))
      (node (ref "R2") (pin "P$2") (pinfunction "P$4_P$2") (pintype "bidirectional"))
      (node (ref "SPK-") (pin "P$1") (pinfunction "P$1_P$1") (pintype "bidirectional"))
      (node (ref "U2") (pin "2") (pinfunction "OUT-_2") (pintype "bidirectional"))
    )
    (net (code "59") (name "Net-(R3-P$3)") (class "Default")
      (node (ref "C11") (pin "P$2") (pinfunction "P$2_P$2") (pintype "bidirectional"))
      (node (ref "R3") (pin "P$1") (pinfunction "P$3_P$1") (pintype "bidirectional"))
    )
    (net (code "60") (name "Net-(R4-P$4)") (class "Default")
      (node (ref "D10_LED") (pin "A") (pinfunction "A_A") (pintype "bidirectional"))
      (node (ref "R4") (pin "P$2") (pinfunction "P$4_P$2") (pintype "bidirectional"))
    )
    (net (code "61") (name "Net-(R5-P$4)") (class "Default")
      (node (ref "PWR_LED") (pin "A") (pinfunction "A_A") (pintype "bidirectional"))
      (node (ref "R5") (pin "P$2") (pinfunction "P$4_P$2") (pintype "bidirectional"))
    )
    (net (code "62") (name "Net-(R6-P$4)") (class "Default")
      (node (ref "D13_LED") (pin "A") (pinfunction "A_A") (pintype "bidirectional"))
      (node (ref "R6") (pin "P$2") (pinfunction "P$4_P$2") (pintype "bidirectional"))
    )
    (net (code "63") (name "Net-(R7-P$4)") (class "Default")
      (node (ref "R7") (pin "P$2") (pinfunction "P$4_P$2") (pintype "bidirectional"))
      (node (ref "TX_LED") (pin "A") (pinfunction "A_A") (pintype "bidirectional"))
    )
    (net (code "64") (name "Net-(R8-P$4)") (class "Default")
      (node (ref "R8") (pin "P$2") (pinfunction "P$4_P$2") (pintype "bidirectional"))
      (node (ref "RX_LED") (pin "A") (pinfunction "A_A") (pintype "bidirectional"))
    )
    (net (code "65") (name "Net-(R9-P$4)") (class "Default")
      (node (ref "J1") (pin "2") (pinfunction "2_2") (pintype "bidirectional"))
      (node (ref "R9") (pin "P$2") (pinfunction "P$4_P$2") (pintype "bidirectional"))
    )
    (net (code "66") (name "Net-(R10-P$4)") (class "Default")
      (node (ref "J1") (pin "3") (pinfunction "3_3") (pintype "bidirectional"))
      (node (ref "R10") (pin "P$2") (pinfunction "P$4_P$2") (pintype "bidirectional"))
    )
    (net (code "67") (name "Net-(R11-P$4)") (class "Default")
      (node (ref "D11_LED") (pin "A") (pinfunction "A_A") (pintype "bidirectional"))
      (node (ref "R11") (pin "P$2") (pinfunction "P$4_P$2") (pintype "bidirectional"))
    )
    (net (code "68") (name "Net-(R12-P$4)") (class "Default")
      (node (ref "D1_LED") (pin "A") (pinfunction "A_A") (pintype "bidirectional"))
      (node (ref "R12") (pin "P$2") (pinfunction "P$4_P$2") (pintype "bidirectional"))
    )
    (net (code "69") (name "Net-(R13-P$4)") (class "Default")
      (node (ref "D0_LED") (pin "A") (pinfunction "A_A") (pintype "bidirectional"))
      (node (ref "R13") (pin "P$2") (pinfunction "P$4_P$2") (pintype "bidirectional"))
    )
    (net (code "70") (name "Net-(U$1-Pad3)") (class "Default")
      (node (ref "U$1") (pin "3") (pinfunction "3_3") (pintype "bidirectional"))
      (node (ref "USB") (pin "VBUS") (pinfunction "VBUS_VBUS") (pintype "power_in"))
    )
    (net (code "71") (name "Net-(U1A-PA00{slash}I0{slash}SERCOM1.0{slash}TC2.0)") (class "Default")
      (node (ref "C5") (pin "1") (pinfunction "1_1") (pintype "passive"))
      (node (ref "U1") (pin "1") (pinfunction "PA00/I0/SERCOM1.0/TC2.0_1") (pintype "bidirectional"))
      (node (ref "X1") (pin "P$1") (pinfunction "P$1_P$1") (pintype "bidirectional"))
    )
    (net (code "72") (name "Net-(U1A-PA01{slash}I1{slash}SERCOM1.1{slash}TC2.1)") (class "Default")
      (node (ref "C7") (pin "1") (pinfunction "1_1") (pintype "passive"))
      (node (ref "U1") (pin "2") (pinfunction "PA01/I1/SERCOM1.1/TC2.1_2") (pintype "bidirectional"))
      (node (ref "X1") (pin "P$2") (pinfunction "P$2_P$2") (pintype "bidirectional"))
    )
    (net (code "73") (name "Net-(U1E-VDDCORE)") (class "Default")
      (node (ref "C21") (pin "P$2") (pinfunction "P$2_P$2") (pintype "bidirectional"))
      (node (ref "C23") (pin "P$2") (pinfunction "P$2_P$2") (pintype "bidirectional"))
      (node (ref "L1") (pin "1") (pinfunction "1_1") (pintype "passive"))
      (node (ref "U1") (pin "115") (pinfunction "VDDCORE_115") (pintype "bidirectional"))
    )
    (net (code "74") (name "Net-(U1E-VSW)") (class "Default")
      (node (ref "L1") (pin "2") (pinfunction "2_2") (pintype "passive"))
      (node (ref "U1") (pin "117") (pinfunction "VSW_117") (pintype "bidirectional"))
    )
    (net (code "75") (name "Net-(U2-BYP)") (class "Default")
      (node (ref "C6") (pin "P$1") (pinfunction "P$1_P$1") (pintype "bidirectional"))
      (node (ref "U2") (pin "1") (pinfunction "IN+_1") (pintype "bidirectional"))
      (node (ref "U2") (pin "5") (pinfunction "BYP_5") (pintype "bidirectional"))
    )
    (net (code "76") (name "Net-(U2-OUT+)") (class "Default")
      (node (ref "SPK+") (pin "P$1") (pinfunction "P$1_P$1") (pintype "bidirectional"))
      (node (ref "U2") (pin "6") (pinfunction "OUT+_6") (pintype "bidirectional"))
    )
    (net (code "77") (name "PA20") (class "Default")
      (node (ref "U$38") (pin "P$1") (pinfunction "1_P$1") (pintype "bidirectional"))
      (node (ref "U1") (pin "88") (pinfunction "PA20/I4/SERCOM3+5.2/I2SFS0/TC7.0+TCC1.4+0.0/PTC_88") (pintype "bidirectional"))
    )
    (net (code "78") (name "PA21") (class "Default")
      (node (ref "U$39") (pin "P$1") (pinfunction "1_P$1") (pintype "bidirectional"))
      (node (ref "U1") (pin "89") (pinfunction "PA21/I5/SERCOM3+5.3/I2SDO/TC7.1+TCC1.5+0.1/PTC_89") (pintype "bidirectional"))
    )
    (net (code "79") (name "PA22") (class "Default")
      (node (ref "U$40") (pin "P$1") (pinfunction "1_P$1") (pintype "bidirectional"))
      (node (ref "U1") (pin "92") (pinfunction "PA22/I2C/16/SERCOM3.0+5.1/I2SDI/TC4.0+TCC1.6+0.2/PTC_92") (pintype "bidirectional"))
    )
    (net (code "80") (name "PA23") (class "Default")
      (node (ref "U$41") (pin "P$1") (pinfunction "1_P$1") (pintype "bidirectional"))
      (node (ref "U1") (pin "93") (pinfunction "PA23/I2C/I7/SERCOM3.1+5.0/SOF/I2SFS1/TC4.1+TCC1.7+0.3/PTC_93") (pintype "bidirectional"))
    )
    (net (code "81") (name "PCC_CLK") (class "Default")
      (node (ref "U1") (pin "62") (pinfunction "PA14/I14/SERCOM2+4.2/TC3.0+TCC2.0+1.2_62") (pintype "bidirectional"))
    )
    (net (code "82") (name "PCC_D0") (class "Default")
      (node (ref "U1") (pin "66") (pinfunction "PA16/I2C/I0/SERCOM1.0+3.1/TC2.0+TCC1.0+0.4/PTC_66") (pintype "bidirectional"))
    )
    (net (code "83") (name "PCC_D1") (class "Default")
      (node (ref "U1") (pin "67") (pinfunction "PA17/I2C/I1/SERCOM1.1+3.0/TC2.1+TCC1.1+0.5/PTC_67") (pintype "bidirectional"))
    )
    (net (code "84") (name "PCC_D2") (class "Default")
      (node (ref "U1") (pin "68") (pinfunction "PA18/I2/SERCOM1+3.2/TC3.0+TCC1.2+0.6/PTC_68") (pintype "bidirectional"))
    )
    (net (code "85") (name "PCC_D3") (class "Default")
      (node (ref "U1") (pin "69") (pinfunction "PA19/I3/SERCOM1+3.3/TC3.1+TCC1.3+0.7/PTC_69") (pintype "bidirectional"))
    )
    (net (code "86") (name "PCC_D8") (class "Default")
      (node (ref "U1") (pin "43") (pinfunction "PB14/I14/SERCOM4.2/PCC8/TC5.0+TCC4.0+0.2/PTC_43") (pintype "bidirectional"))
    )
    (net (code "87") (name "PCC_D9") (class "Default")
      (node (ref "U1") (pin "44") (pinfunction "PB15/I15/SERCOM4.3/PCC9/TC5.1/TCC4.1+0.3/PTC_44") (pintype "bidirectional"))
    )
    (net (code "88") (name "PCC_D10") (class "Default")
      (node (ref "U1") (pin "56") (pinfunction "PC12/I12/SERCOM7.0+6.1/TCC0.2+1.6_56") (pintype "bidirectional"))
    )
    (net (code "89") (name "PCC_D11") (class "Default")
      (node (ref "U1") (pin "57") (pinfunction "PC13/I13/SERCOM7.1+6.0/TCC0.3+1.7_57") (pintype "bidirectional"))
    )
    (net (code "90") (name "PCC_D12") (class "Default")
      (node (ref "U1") (pin "58") (pinfunction "PC14/I14/SERCOM7+6.2/TCC0.4+1.0_58") (pintype "bidirectional"))
    )
    (net (code "91") (name "PCC_D13") (class "Default")
      (node (ref "U1") (pin "59") (pinfunction "PC15/I15/SERCOM7+6.3/TCC0.5+1.1_59") (pintype "bidirectional"))
    )
    (net (code "92") (name "PCC_DEN1") (class "Default")
      (node (ref "U1") (pin "60") (pinfunction "PA12/I12/I2C/SERCOM2.0+4.1/TC2.0+TCC0.7+1.3_60") (pintype "bidirectional"))
    )
    (net (code "93") (name "PCC_DEN2") (class "Default")
      (node (ref "U1") (pin "61") (pinfunction "PA13/I13/I2C/SERCOM2.1+4.0/TC2.1+TCC0.7+1.3_61") (pintype "bidirectional"))
    )
    (net (code "94") (name "PCC_XCLK") (class "Default")
      (node (ref "U1") (pin "85") (pinfunction "PB19/I3/SERCOM5+7.3/CC1.1/QDI.1_85") (pintype "bidirectional"))
    )
    (net (code "95") (name "RXLED") (class "Default")
      (node (ref "R8") (pin "P$1") (pinfunction "P$3_P$1") (pintype "bidirectional"))
      (node (ref "U1") (pin "124") (pinfunction "PC31/I15/AIN1.13_124") (pintype "bidirectional"))
    )
    (net (code "96") (name "SCK") (class "Default")
      (node (ref "U1") (pin "48") (pinfunction "PD09/I4/SERCOM7.1+6.0/TCC0.2_48") (pintype "bidirectional"))
    )
    (net (code "97") (name "SCL") (class "Default")
      (node (ref "U1") (pin "87") (pinfunction "PB21/SERCOM3.1+7.0/TCC1.3_87") (pintype "bidirectional"))
    )
    (net (code "98") (name "SCL_1") (class "Default")
      (node (ref "U1") (pin "71") (pinfunction "PC17/I1/SERCOM6.1+0.0/TCC0.1/QDI.1_71") (pintype "bidirectional"))
    )
    (net (code "99") (name "SDA") (class "Default")
      (node (ref "U1") (pin "86") (pinfunction "PB20/I4/SERCOM3.0+7.1/TCC1.2/QDI.2_86") (pintype "bidirectional"))
    )
    (net (code "100") (name "SDA_1") (class "Default")
      (node (ref "U1") (pin "70") (pinfunction "PC16/I0/SERCOM6.0+0.1/TCC0/QDI.0_70") (pintype "bidirectional"))
    )
    (net (code "101") (name "SD_CD") (class "Default")
      (node (ref "U1") (pin "122") (pinfunction "PB31/I15/SERCOM5.0/TC0.1+TCC4.1+0.7_122") (pintype "bidirectional"))
    )
    (net (code "102") (name "SD_CS") (class "Default")
      (node (ref "U1") (pin "104") (pinfunction "PB28/I14/SEROM2+4.2/TCC1.4/I2SSCK.1_104") (pintype "bidirectional"))
    )
    (net (code "103") (name "SD_MISO") (class "Default")
      (node (ref "U1") (pin "105") (pinfunction "PB29/I15/SERCOM2+4.3/TCC1.5/I2SMCK.1_105") (pintype "bidirectional"))
    )
    (net (code "104") (name "SD_MOSI") (class "Default")
      (node (ref "U1") (pin "102") (pinfunction "PB26/I12/SERCOM2.0+4.1/TCC1.3_102") (pintype "bidirectional"))
    )
    (net (code "105") (name "SD_SCK") (class "Default")
      (node (ref "U1") (pin "103") (pinfunction "PB27/I13/SERCOM2.1+4.0/TCC1.3_103") (pintype "bidirectional"))
    )
    (net (code "106") (name "SS") (class "Default")
      (node (ref "U1") (pin "49") (pinfunction "PD10/I5/SERCOM7+6.2/TCC0.3_49") (pintype "bidirectional"))
    )
    (net (code "107") (name "SWCLK") (class "Default")
      (node (ref "J2") (pin "3") (pinfunction "3_3") (pintype "bidirectional"))
      (node (ref "U1") (pin "119") (pinfunction "PA30/I14/SERCOM1.2/SWCLK_119") (pintype "bidirectional"))
    )
    (net (code "108") (name "SWDIO") (class "Default")
      (node (ref "J2") (pin "4") (pinfunction "4_4") (pintype "bidirectional"))
      (node (ref "U1") (pin "120") (pinfunction "PA31/I15/SERCOM1.3/SWDIO_120") (pintype "bidirectional"))
    )
    (net (code "109") (name "SWO") (class "Default")
      (node (ref "U1") (pin "121") (pinfunction "PB30/I14/SERCOM5.1/TC0.0+TCC4.0+0.6/SWO_121") (pintype "bidirectional"))
    )
    (net (code "110") (name "TXLED") (class "Default")
      (node (ref "R7") (pin "P$1") (pinfunction "P$3_P$1") (pintype "bidirectional"))
      (node (ref "U1") (pin "123") (pinfunction "PC30/I14/AIN1.12_123") (pintype "bidirectional"))
    )
    (net (code "111") (name "UART1_RX") (class "Default")
      (node (ref "R9") (pin "P$1") (pinfunction "P$3_P$1") (pintype "bidirectional"))
      (node (ref "U1") (pin "42") (pinfunction "PB13/I13/SERCOM4.1/I2SMCK1/TC4.1+TCC3.1+0.1/PTC_42") (pintype "bidirectional"))
    )
    (net (code "112") (name "UART1_TX") (class "Default")
      (node (ref "R10") (pin "P$1") (pinfunction "P$3_P$1") (pintype "bidirectional"))
      (node (ref "U1") (pin "41") (pinfunction "PB12/I12/SERCOM4.0/I2SCK1/TC4.0+TCC3.0+0.1/PTC_41") (pintype "bidirectional"))
    )
    (net (code "113") (name "UART2_RX") (class "Default")
      (node (ref "U1") (pin "77") (pinfunction "PC23/I7/SERCOM1.1+3.0/TCC0.7_77") (pintype "bidirectional"))
    )
    (net (code "114") (name "UART2_TX") (class "Default")
      (node (ref "U1") (pin "76") (pinfunction "PC22/I6/SERCOM1.0+3.1/TCC0.6_76") (pintype "bidirectional"))
    )
    (net (code "115") (name "UART3_RX") (class "Default")
      (node (ref "U1") (pin "83") (pinfunction "PB17/SERCOM5.1/I2SMCK0/TC6.1+TCC3.1+0.5_83") (pintype "bidirectional"))
    )
    (net (code "116") (name "UART3_TX") (class "Default")
      (node (ref "U1") (pin "82") (pinfunction "PB16/I0/SERCOM5.0/I2SCK0/TC6.0+TCC3.0+0.4_82") (pintype "bidirectional"))
    )
    (net (code "117") (name "USB_HOSTEN") (class "Default")
      (node (ref "U1") (pin "113") (pinfunction "PA27/I11_113") (pintype "bidirectional"))
    )
    (net (code "118") (name "unconnected-(U1C-PC25{slash}I9{slash}SERCOM0+2.3{slash}TRACEDATA.2-Pad109)") (class "Default")
      (node (ref "U1") (pin "109") (pinfunction "PC25/I9/SERCOM0+2.3/TRACEDATA.2_109") (pintype "bidirectional"))
    )
    (net (code "119") (name "unconnected-(U1C-PC26{slash}I10{slash}TRACEDATA.1-Pad110)") (class "Default")
      (node (ref "U1") (pin "110") (pinfunction "PC26/I10/TRACEDATA.1_110") (pintype "bidirectional"))
    )
    (net (code "120") (name "unconnected-(U1C-PC27{slash}I11{slash}SERCOM1.0{slash}TRACECLK-Pad111)") (class "Default")
      (node (ref "U1") (pin "111") (pinfunction "PC27/I11/SERCOM1.0/TRACECLK_111") (pintype "bidirectional"))
    )
    (net (code "121") (name "unconnected-(U1C-PC28{slash}I12{slash}SERCOM1.1{slash}TRACEDATA.0-Pad112)") (class "Default")
      (node (ref "U1") (pin "112") (pinfunction "PC28/I12/SERCOM1.1/TRACEDATA.0_112") (pintype "bidirectional"))
    )
    (net (code "122") (name "unconnected-(U1D-PD00{slash}I0{slash}AIN1.14-Pad13)") (class "Default")
      (node (ref "U1") (pin "13") (pinfunction "PD00/I0/AIN1.14_13") (pintype "bidirectional"))
    )
    (net (code "123") (name "unconnected-(U1D-PD01{slash}I1{slash}AIN1.14-Pad16)") (class "Default")
      (node (ref "U1") (pin "16") (pinfunction "PD01/I1/AIN1.14_16") (pintype "bidirectional"))
    )
    (net (code "124") (name "unconnected-(USB-PadID)") (class "Default")
      (node (ref "USB") (pin "ID") (pinfunction "ID_ID") (pintype "bidirectional"))
    )
    (net (code "125") (name "unconnected-(USB-SHIELD-PadP$4)") (class "Default")
      (node (ref "USB") (pin "P$4") (pinfunction "SHIELD_P$4") (pintype "bidirectional"))
    )
    (net (code "126") (name "~{RESET}") (class "Default")
      (node (ref "C22") (pin "P$2") (pinfunction "P$2_P$2") (pintype "bidirectional"))
      (node (ref "J2") (pin "2") (pinfunction "2_2") (pintype "bidirectional"))
      (node (ref "R1") (pin "P$2") (pinfunction "P$4_P$2") (pintype "bidirectional"))
      (node (ref "SW1") (pin "P$3") (pinfunction "P$2_P$3") (pintype "bidirectional"))
      (node (ref "SW1") (pin "P$4") (pinfunction "P$2_P$4") (pintype "bidirectional"))
      (node (ref "U1") (pin "114") (pinfunction "~{RESET}_114") (pintype "bidirectional"))
    )
  )
)
